# BuchlaBusBoard.net
KiCad netlist of a schematic drawn in Altium Designer
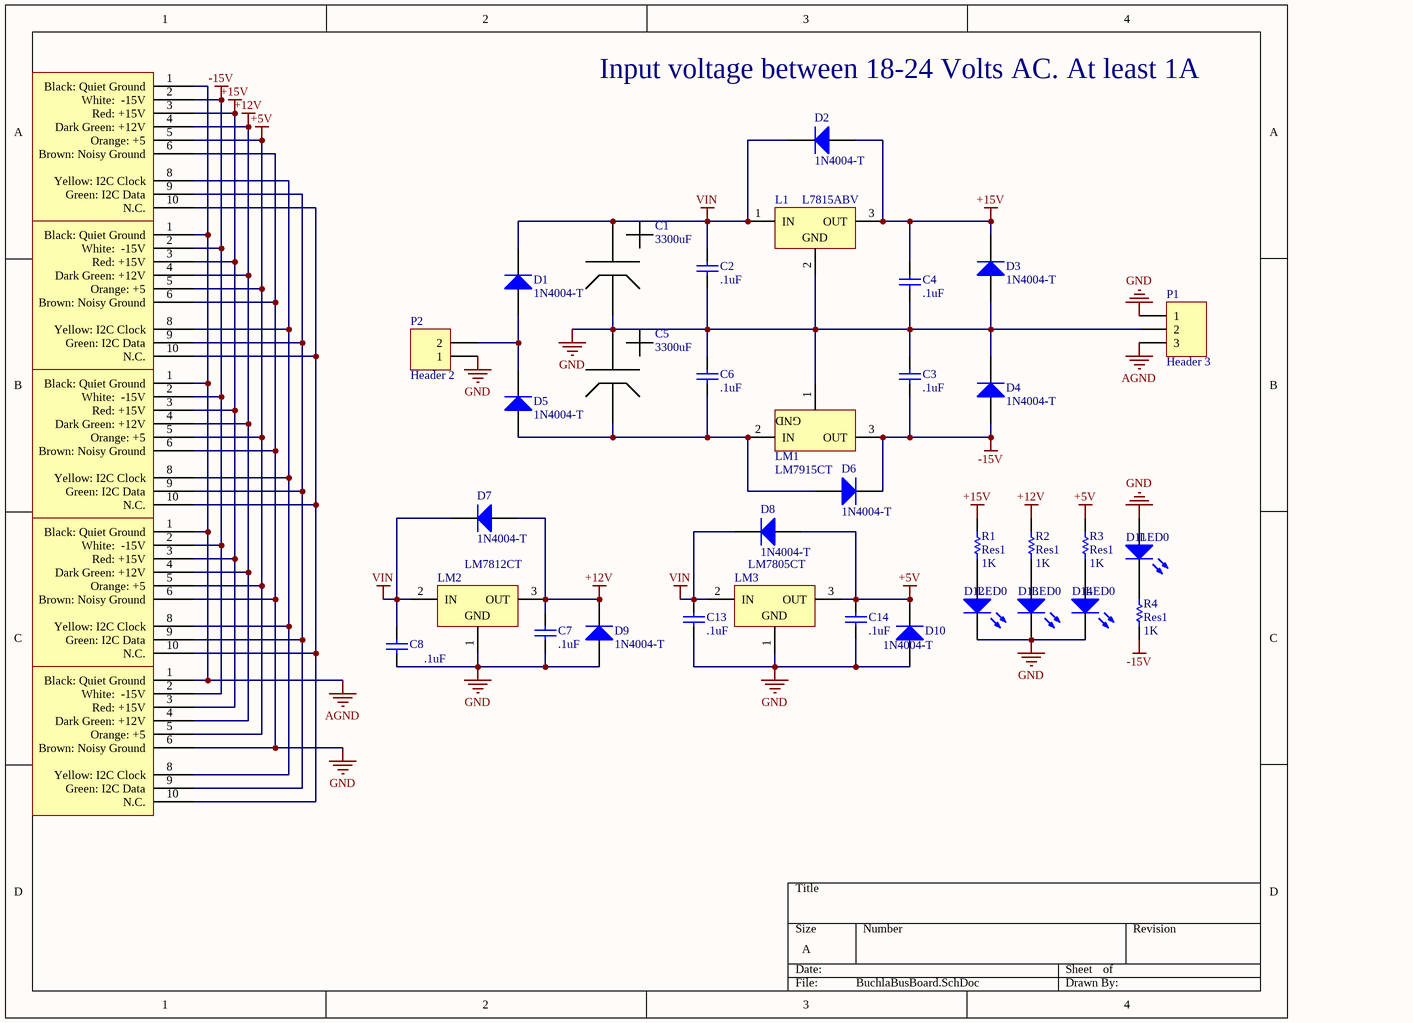
[diagram p0: BuchlaBusBoard.SchDoc]

(export (version "E")
  (design (tool "Eeschema 10.0.6"))
  (components
    (comp (ref "C1")
      (value "3300uF")
      (footprint "100uF")
      (description "100uF Electrolytic")
      (fields (field (name "MFR") "Illinois"))
      (libsource (lib "BuchlaBusBoardLibrary") (part "100uF Sprague"))
    )
    (comp (ref "C2")
      (value ".1uF")
      (footprint ".1uF")
      (description ".1uF Cap")
      (fields (field (name "MFR") "Vishay") (field (name "PUBLISHER") "Altium Limited"))
      (libsource (lib "Miscellaneous Devices") (part "Cap"))
    )
    (comp (ref "C3")
      (value ".1uF")
      (footprint ".1uF")
      (description ".1uF Cap")
      (fields (field (name "MFR") "Vishay") (field (name "PUBLISHER") "Altium Limited"))
      (libsource (lib "Miscellaneous Devices") (part "Cap"))
    )
    (comp (ref "C4")
      (value ".1uF")
      (footprint ".1uF")
      (description ".1uF Cap")
      (fields (field (name "MFR") "Vishay") (field (name "PUBLISHER") "Altium Limited"))
      (libsource (lib "Miscellaneous Devices") (part "Cap"))
    )
    (comp (ref "C5")
      (value "3300uF")
      (footprint "100uF")
      (description "100uF Electrolytic")
      (fields (field (name "MFR") "Illinois"))
      (libsource (lib "BuchlaBusBoardLibrary") (part "100uF Sprague"))
    )
    (comp (ref "C6")
      (value ".1uF")
      (footprint ".1uF")
      (description ".1uF Cap")
      (fields (field (name "MFR") "Vishay") (field (name "PUBLISHER") "Altium Limited"))
      (libsource (lib "Miscellaneous Devices") (part "Cap"))
    )
    (comp (ref "C7")
      (value ".1uF")
      (footprint ".1uF")
      (description ".1uF Cap")
      (fields (field (name "MFR") "Vishay") (field (name "PUBLISHER") "Altium Limited"))
      (libsource (lib "Miscellaneous Devices") (part "Cap"))
    )
    (comp (ref "C8")
      (value ".1uF")
      (footprint ".1uF")
      (description ".1uF Cap")
      (fields (field (name "MFR") "Vishay") (field (name "PUBLISHER") "Altium Limited"))
      (libsource (lib "Miscellaneous Devices") (part "Cap"))
    )
    (comp (ref "C13")
      (value ".1uF")
      (footprint ".1uF")
      (description ".1uF Cap")
      (fields (field (name "MFR") "Vishay") (field (name "PUBLISHER") "Altium Limited"))
      (libsource (lib "Miscellaneous Devices") (part "Cap"))
    )
    (comp (ref "C14")
      (value ".1uF")
      (footprint ".1uF")
      (description ".1uF Cap")
      (fields (field (name "MFR") "Vishay") (field (name "PUBLISHER") "Altium Limited"))
      (libsource (lib "Miscellaneous Devices") (part "Cap"))
    )
    (comp (ref "D1")
      (value "1N4004-T")
      (footprint "DIOD-DO-41-P-2_V")
      (description "1.0 A Rectifier, 15 pF, 50 V, -65 to 150 degC, 2-Pin DO-41 Plastic, RoHS, Tape and Reel")
      (fields (field (name "MFR") "Diodes Inc"))
      (libsource (lib "Altium Content Vault") (part "CMP-0639-00006-2"))
    )
    (comp (ref "D2")
      (value "1N4004-T")
      (footprint "DIOD-DO-41-P-2_V")
      (description "1.0 A Rectifier, 15 pF, 50 V, -65 to 150 degC, 2-Pin DO-41 Plastic, RoHS, Tape and Reel")
      (fields (field (name "MFR") "Diodes Inc"))
      (libsource (lib "Altium Content Vault") (part "CMP-0639-00006-2"))
    )
    (comp (ref "D3")
      (value "1N4004-T")
      (footprint "DIOD-DO-41-P-2_V")
      (description "1.0 A Rectifier, 15 pF, 50 V, -65 to 150 degC, 2-Pin DO-41 Plastic, RoHS, Tape and Reel")
      (fields (field (name "MFR") "Diodes Inc"))
      (libsource (lib "Altium Content Vault") (part "CMP-0639-00006-2"))
    )
    (comp (ref "D4")
      (value "1N4004-T")
      (footprint "DIOD-DO-41-P-2_V")
      (description "1.0 A Rectifier, 15 pF, 50 V, -65 to 150 degC, 2-Pin DO-41 Plastic, RoHS, Tape and Reel")
      (fields (field (name "MFR") "Diodes Inc"))
      (libsource (lib "Altium Content Vault") (part "CMP-0639-00006-2"))
    )
    (comp (ref "D5")
      (value "1N4004-T")
      (footprint "DIOD-DO-41-P-2_V")
      (description "1.0 A Rectifier, 15 pF, 50 V, -65 to 150 degC, 2-Pin DO-41 Plastic, RoHS, Tape and Reel")
      (fields (field (name "MFR") "Diodes Inc"))
      (libsource (lib "Altium Content Vault") (part "CMP-0639-00006-2"))
    )
    (comp (ref "D6")
      (value "1N4004-T")
      (footprint "DIOD-DO-41-P-2_V")
      (description "1.0 A Rectifier, 15 pF, 50 V, -65 to 150 degC, 2-Pin DO-41 Plastic, RoHS, Tape and Reel")
      (fields (field (name "MFR") "Diodes Inc"))
      (libsource (lib "Altium Content Vault") (part "CMP-0639-00006-2"))
    )
    (comp (ref "D7")
      (value "1N4004-T")
      (footprint "DIOD-DO-41-P-2_V")
      (description "1.0 A Rectifier, 15 pF, 50 V, -65 to 150 degC, 2-Pin DO-41 Plastic, RoHS, Tape and Reel")
      (fields (field (name "MFR") "Diodes Inc"))
      (libsource (lib "Altium Content Vault") (part "CMP-0639-00006-2"))
    )
    (comp (ref "D8")
      (value "1N4004-T")
      (footprint "DIOD-DO-41-P-2_V")
      (description "1.0 A Rectifier, 15 pF, 50 V, -65 to 150 degC, 2-Pin DO-41 Plastic, RoHS, Tape and Reel")
      (fields (field (name "MFR") "Diodes Inc"))
      (libsource (lib "Altium Content Vault") (part "CMP-0639-00006-2"))
    )
    (comp (ref "D9")
      (value "1N4004-T")
      (footprint "DIOD-DO-41-P-2_V")
      (description "1.0 A Rectifier, 15 pF, 50 V, -65 to 150 degC, 2-Pin DO-41 Plastic, RoHS, Tape and Reel")
      (fields (field (name "MFR") "Diodes Inc"))
      (libsource (lib "Altium Content Vault") (part "CMP-0639-00006-2"))
    )
    (comp (ref "D10")
      (value "1N4004-T")
      (footprint "DIOD-DO-41-P-2_V")
      (description "1.0 A Rectifier, 15 pF, 50 V, -65 to 150 degC, 2-Pin DO-41 Plastic, RoHS, Tape and Reel")
      (fields (field (name "MFR") "Diodes Inc"))
      (libsource (lib "Altium Content Vault") (part "CMP-0639-00006-2"))
    )
    (comp (ref "D11")
      (value "LED0")
      (footprint "LED-0")
      (description "Typical INFRARED GaAs LED")
      (fields (field (name "PUBLISHER") "Altium Limited"))
      (libsource (lib "Miscellaneous Devices") (part "LED0"))
    )
    (comp (ref "D12")
      (value "LED0")
      (footprint "LED-0")
      (description "Typical INFRARED GaAs LED")
      (fields (field (name "PUBLISHER") "Altium Limited"))
      (libsource (lib "Miscellaneous Devices") (part "LED0"))
    )
    (comp (ref "D13")
      (value "LED0")
      (footprint "LED-0")
      (description "Typical INFRARED GaAs LED")
      (fields (field (name "PUBLISHER") "Altium Limited"))
      (libsource (lib "Miscellaneous Devices") (part "LED0"))
    )
    (comp (ref "D14")
      (value "LED0")
      (footprint "LED-0")
      (description "Typical INFRARED GaAs LED")
      (fields (field (name "PUBLISHER") "Altium Limited"))
      (libsource (lib "Miscellaneous Devices") (part "LED0"))
    )
    (comp (ref "L1")
      (value "L7815ABV")
      (footprint "TO220")
      (description "15V Positive Regulator")
      (fields (field (name "MFR") "ST"))
      (libsource (lib "Altium Content Vault") (part "CMP-0244-00468-1"))
    )
    (comp (ref "LM1")
      (value "LM7915CT")
      (footprint "NDE0003A")
      (description "3-Terminal Negative Regulator, 3-pin TO-220")
      (fields (field (name "MANUFACTURER") "Texas Instruments"))
      (libsource (lib "altium-import") (part "root_2_mirrored_CMP-0062-02471-3_"))
    )
    (comp (ref "LM2")
      (value "LM7812CT")
      (footprint "NDE0003A")
      (description "3-Terminal Negative Regulator, 3-pin TO-220")
      (fields (field (name "MANUFACTURER") "Texas Instruments"))
      (libsource (lib "altium-import") (part "root_0_CMP-0062-02471-3_"))
    )
    (comp (ref "LM3")
      (value "LM7805CT")
      (footprint "NDE0003A")
      (description "3-Terminal Negative Regulator, 3-pin TO-220")
      (fields (field (name "MANUFACTURER") "Texas Instruments"))
      (libsource (lib "altium-import") (part "root_0_CMP-0062-02471-3_"))
    )
    (comp (ref "P1")
      (value "Header 3")
      (footprint "HDR1X3")
      (description "Header, 3-Pin")
      (fields (field (name "PUBLISHER") "Altium Limited"))
      (libsource (lib "Miscellaneous Connectors") (part "Header 3"))
    )
    (comp (ref "P2")
      (value "Header 2")
      (footprint "HDR1X2")
      (description "Header, 2-Pin")
      (fields (field (name "PUBLISHER") "Altium Limited"))
      (libsource (lib "Miscellaneous Connectors") (part "Header 2"))
    )
    (comp (ref "R1")
      (value "Res1")
      (footprint "AXIAL-0.3")
      (description "Resistor")
      (fields (field (name "ALTIUM_VALUE") "1K") (field (name "PUBLISHER") "Altium Limited"))
      (libsource (lib "Miscellaneous Devices") (part "Res1"))
    )
    (comp (ref "R2")
      (value "Res1")
      (footprint "AXIAL-0.3")
      (description "Resistor")
      (fields (field (name "ALTIUM_VALUE") "1K") (field (name "PUBLISHER") "Altium Limited"))
      (libsource (lib "Miscellaneous Devices") (part "Res1"))
    )
    (comp (ref "R3")
      (value "Res1")
      (footprint "AXIAL-0.3")
      (description "Resistor")
      (fields (field (name "ALTIUM_VALUE") "1K") (field (name "PUBLISHER") "Altium Limited"))
      (libsource (lib "Miscellaneous Devices") (part "Res1"))
    )
    (comp (ref "R4")
      (value "Res1")
      (footprint "AXIAL-0.3")
      (description "Resistor")
      (fields (field (name "ALTIUM_VALUE") "1K") (field (name "PUBLISHER") "Altium Limited"))
      (libsource (lib "Miscellaneous Devices") (part "Res1"))
    )
    (comp (ref "Vag1")
      (value "Component_1")
      (footprint "BuchlaPower")
      (libsource (lib "BuchlaBusBoardLibrary") (part "Component_1"))
    )
    (comp (ref "Vag2")
      (value "Component_1")
      (footprint "BuchlaPower")
      (libsource (lib "BuchlaBusBoardLibrary") (part "Component_1"))
    )
    (comp (ref "Vag5")
      (value "Component_1")
      (footprint "BuchlaPower")
      (libsource (lib "BuchlaBusBoardLibrary") (part "Component_1"))
    )
    (comp (ref "Vag6")
      (value "Component_1")
      (footprint "BuchlaPower")
      (libsource (lib "BuchlaBusBoardLibrary") (part "Component_1"))
    )
    (comp (ref "Vag7")
      (value "Component_1")
      (footprint "BuchlaPower")
      (libsource (lib "BuchlaBusBoardLibrary") (part "Component_1"))
    )
  )
  (nets
    (net (code "1") (name "+5V") (class "Default")
      (node (ref "C14") (pin "2") (pinfunction "2_2") (pintype "passive"))
      (node (ref "D10") (pin "2") (pinfunction "K_2") (pintype "passive"))
      (node (ref "D8") (pin "1") (pinfunction "A_1") (pintype "passive"))
      (node (ref "LM3") (pin "3") (pinfunction "OUT_3") (pintype "power_in"))
      (node (ref "R3") (pin "2") (pinfunction "2_2") (pintype "passive"))
      (node (ref "Vag1") (pin "5") (pinfunction "Orange:_+5_5") (pintype "passive"))
      (node (ref "Vag2") (pin "5") (pinfunction "Orange:_+5_5") (pintype "passive"))
      (node (ref "Vag5") (pin "5") (pinfunction "Orange:_+5_5") (pintype "passive"))
      (node (ref "Vag6") (pin "5") (pinfunction "Orange:_+5_5") (pintype "passive"))
      (node (ref "Vag7") (pin "5") (pinfunction "Orange:_+5_5") (pintype "passive"))
    )
    (net (code "2") (name "+12V") (class "Default")
      (node (ref "C7") (pin "2") (pinfunction "2_2") (pintype "passive"))
      (node (ref "D7") (pin "1") (pinfunction "A_1") (pintype "passive"))
      (node (ref "D9") (pin "2") (pinfunction "K_2") (pintype "passive"))
      (node (ref "LM2") (pin "3") (pinfunction "OUT_3") (pintype "power_in"))
      (node (ref "R2") (pin "2") (pinfunction "2_2") (pintype "passive"))
      (node (ref "Vag1") (pin "4") (pinfunction "Dark_Green:_+12V_4") (pintype "passive"))
      (node (ref "Vag2") (pin "4") (pinfunction "Dark_Green:_+12V_4") (pintype "passive"))
      (node (ref "Vag5") (pin "4") (pinfunction "Dark_Green:_+12V_4") (pintype "passive"))
      (node (ref "Vag6") (pin "4") (pinfunction "Dark_Green:_+12V_4") (pintype "passive"))
      (node (ref "Vag7") (pin "4") (pinfunction "Dark_Green:_+12V_4") (pintype "passive"))
    )
    (net (code "3") (name "+15V") (class "Default")
      (node (ref "C4") (pin "2") (pinfunction "2_2") (pintype "passive"))
      (node (ref "D2") (pin "1") (pinfunction "A_1") (pintype "passive"))
      (node (ref "D3") (pin "2") (pinfunction "K_2") (pintype "passive"))
      (node (ref "L1") (pin "3") (pinfunction "OUT_3") (pintype "power_in"))
      (node (ref "R1") (pin "2") (pinfunction "2_2") (pintype "passive"))
      (node (ref "Vag1") (pin "3") (pinfunction "Red:_+15V_3") (pintype "passive"))
      (node (ref "Vag2") (pin "3") (pinfunction "Red:_+15V_3") (pintype "passive"))
      (node (ref "Vag5") (pin "3") (pinfunction "Red:_+15V_3") (pintype "passive"))
      (node (ref "Vag6") (pin "3") (pinfunction "Red:_+15V_3") (pintype "passive"))
      (node (ref "Vag7") (pin "3") (pinfunction "Red:_+15V_3") (pintype "passive"))
    )
    (net (code "4") (name "-15V") (class "Default")
      (node (ref "C3") (pin "1") (pinfunction "1_1") (pintype "passive"))
      (node (ref "D4") (pin "1") (pinfunction "A_1") (pintype "passive"))
      (node (ref "D6") (pin "2") (pinfunction "K_2") (pintype "passive"))
      (node (ref "LM1") (pin "3") (pinfunction "OUT_3") (pintype "power_in"))
      (node (ref "R4") (pin "1") (pinfunction "1_1") (pintype "passive"))
      (node (ref "Vag1") (pin "2") (pinfunction "White:__-15V_2") (pintype "passive"))
      (node (ref "Vag2") (pin "2") (pinfunction "White:__-15V_2") (pintype "passive"))
      (node (ref "Vag5") (pin "2") (pinfunction "White:__-15V_2") (pintype "passive"))
      (node (ref "Vag6") (pin "2") (pinfunction "White:__-15V_2") (pintype "passive"))
      (node (ref "Vag7") (pin "2") (pinfunction "White:__-15V_2") (pintype "passive"))
    )
    (net (code "5") (name "AGND") (class "Default")
      (node (ref "P1") (pin "3") (pinfunction "3_3") (pintype "passive"))
      (node (ref "Vag1") (pin "1") (pinfunction "Black:_Quiet_Ground_1") (pintype "passive"))
      (node (ref "Vag2") (pin "1") (pinfunction "Black:_Quiet_Ground_1") (pintype "passive"))
      (node (ref "Vag5") (pin "1") (pinfunction "Black:_Quiet_Ground_1") (pintype "passive"))
      (node (ref "Vag6") (pin "1") (pinfunction "Black:_Quiet_Ground_1") (pintype "passive"))
      (node (ref "Vag7") (pin "1") (pinfunction "Black:_Quiet_Ground_1") (pintype "passive"))
    )
    (net (code "6") (name "GND") (class "Default")
      (node (ref "C1") (pin "1") (pinfunction "33_1") (pintype "passive"))
      (node (ref "C13") (pin "1") (pinfunction "1_1") (pintype "passive"))
      (node (ref "C14") (pin "1") (pinfunction "1_1") (pintype "passive"))
      (node (ref "C2") (pin "1") (pinfunction "1_1") (pintype "passive"))
      (node (ref "C3") (pin "2") (pinfunction "2_2") (pintype "passive"))
      (node (ref "C4") (pin "1") (pinfunction "1_1") (pintype "passive"))
      (node (ref "C5") (pin "0") (pinfunction "32_0") (pintype "passive"))
      (node (ref "C6") (pin "2") (pinfunction "2_2") (pintype "passive"))
      (node (ref "C7") (pin "1") (pinfunction "1_1") (pintype "passive"))
      (node (ref "C8") (pin "1") (pinfunction "1_1") (pintype "passive"))
      (node (ref "D10") (pin "1") (pinfunction "A_1") (pintype "passive"))
      (node (ref "D11") (pin "1") (pinfunction "A_1") (pintype "passive"))
      (node (ref "D12") (pin "2") (pinfunction "K_2") (pintype "passive"))
      (node (ref "D13") (pin "2") (pinfunction "K_2") (pintype "passive"))
      (node (ref "D14") (pin "2") (pinfunction "K_2") (pintype "passive"))
      (node (ref "D3") (pin "1") (pinfunction "A_1") (pintype "passive"))
      (node (ref "D4") (pin "2") (pinfunction "K_2") (pintype "passive"))
      (node (ref "D9") (pin "1") (pinfunction "A_1") (pintype "passive"))
      (node (ref "L1") (pin "2") (pinfunction "GND_2") (pintype "power_in"))
      (node (ref "LM1") (pin "1") (pinfunction "GND_1") (pintype "power_in"))
      (node (ref "LM2") (pin "1") (pinfunction "GND_1") (pintype "power_in"))
      (node (ref "LM3") (pin "1") (pinfunction "GND_1") (pintype "power_in"))
      (node (ref "P1") (pin "1") (pinfunction "1_1") (pintype "passive"))
      (node (ref "P1") (pin "2") (pinfunction "2_2") (pintype "passive"))
      (node (ref "P2") (pin "1") (pinfunction "1_1") (pintype "passive"))
      (node (ref "Vag1") (pin "6") (pinfunction "Brown:_Noisy_Ground_6") (pintype "passive"))
      (node (ref "Vag2") (pin "6") (pinfunction "Brown:_Noisy_Ground_6") (pintype "passive"))
      (node (ref "Vag5") (pin "6") (pinfunction "Brown:_Noisy_Ground_6") (pintype "passive"))
      (node (ref "Vag6") (pin "6") (pinfunction "Brown:_Noisy_Ground_6") (pintype "passive"))
      (node (ref "Vag7") (pin "6") (pinfunction "Brown:_Noisy_Ground_6") (pintype "passive"))
    )
    (net (code "7") (name "Net-(C5-33)") (class "Default")
      (node (ref "C5") (pin "1") (pinfunction "33_1") (pintype "passive"))
      (node (ref "C6") (pin "1") (pinfunction "1_1") (pintype "passive"))
      (node (ref "D5") (pin "1") (pinfunction "A_1") (pintype "passive"))
      (node (ref "D6") (pin "1") (pinfunction "A_1") (pintype "passive"))
      (node (ref "LM1") (pin "2") (pinfunction "IN_2") (pintype "power_in"))
    )
    (net (code "8") (name "Net-(D1-A)") (class "Default")
      (node (ref "D1") (pin "1") (pinfunction "A_1") (pintype "passive"))
      (node (ref "D5") (pin "2") (pinfunction "K_2") (pintype "passive"))
      (node (ref "P2") (pin "2") (pinfunction "2_2") (pintype "passive"))
    )
    (net (code "9") (name "Net-(D11-K)") (class "Default")
      (node (ref "D11") (pin "2") (pinfunction "K_2") (pintype "passive"))
      (node (ref "R4") (pin "2") (pinfunction "2_2") (pintype "passive"))
    )
    (net (code "10") (name "Net-(D12-A)") (class "Default")
      (node (ref "D12") (pin "1") (pinfunction "A_1") (pintype "passive"))
      (node (ref "R1") (pin "1") (pinfunction "1_1") (pintype "passive"))
    )
    (net (code "11") (name "Net-(D13-A)") (class "Default")
      (node (ref "D13") (pin "1") (pinfunction "A_1") (pintype "passive"))
      (node (ref "R2") (pin "1") (pinfunction "1_1") (pintype "passive"))
    )
    (net (code "12") (name "Net-(D14-A)") (class "Default")
      (node (ref "D14") (pin "1") (pinfunction "A_1") (pintype "passive"))
      (node (ref "R3") (pin "1") (pinfunction "1_1") (pintype "passive"))
    )
    (net (code "13") (name "Net-(Vag1-Green:_I2C_Data)") (class "Default")
      (node (ref "Vag1") (pin "9") (pinfunction "Green:_I2C_Data_9") (pintype "passive"))
      (node (ref "Vag2") (pin "9") (pinfunction "Green:_I2C_Data_9") (pintype "passive"))
      (node (ref "Vag5") (pin "9") (pinfunction "Green:_I2C_Data_9") (pintype "passive"))
      (node (ref "Vag6") (pin "9") (pinfunction "Green:_I2C_Data_9") (pintype "passive"))
      (node (ref "Vag7") (pin "9") (pinfunction "Green:_I2C_Data_9") (pintype "passive"))
    )
    (net (code "14") (name "Net-(Vag1-N.C.)") (class "Default")
      (node (ref "Vag1") (pin "10") (pinfunction "N.C._10") (pintype "passive"))
      (node (ref "Vag2") (pin "10") (pinfunction "N.C._10") (pintype "passive"))
      (node (ref "Vag5") (pin "10") (pinfunction "N.C._10") (pintype "passive"))
      (node (ref "Vag6") (pin "10") (pinfunction "N.C._10") (pintype "passive"))
      (node (ref "Vag7") (pin "10") (pinfunction "N.C._10") (pintype "passive"))
    )
    (net (code "15") (name "Net-(Vag1-Yellow:_I2C_Clock)") (class "Default")
      (node (ref "Vag1") (pin "8") (pinfunction "Yellow:_I2C_Clock_8") (pintype "passive"))
      (node (ref "Vag2") (pin "8") (pinfunction "Yellow:_I2C_Clock_8") (pintype "passive"))
      (node (ref "Vag5") (pin "8") (pinfunction "Yellow:_I2C_Clock_8") (pintype "passive"))
      (node (ref "Vag6") (pin "8") (pinfunction "Yellow:_I2C_Clock_8") (pintype "passive"))
      (node (ref "Vag7") (pin "8") (pinfunction "Yellow:_I2C_Clock_8") (pintype "passive"))
    )
    (net (code "16") (name "VIN") (class "Default")
      (node (ref "C1") (pin "0") (pinfunction "32_0") (pintype "passive"))
      (node (ref "C13") (pin "2") (pinfunction "2_2") (pintype "passive"))
      (node (ref "C2") (pin "2") (pinfunction "2_2") (pintype "passive"))
      (node (ref "C8") (pin "2") (pinfunction "2_2") (pintype "passive"))
      (node (ref "D1") (pin "2") (pinfunction "K_2") (pintype "passive"))
      (node (ref "D2") (pin "2") (pinfunction "K_2") (pintype "passive"))
      (node (ref "D7") (pin "2") (pinfunction "K_2") (pintype "passive"))
      (node (ref "D8") (pin "2") (pinfunction "K_2") (pintype "passive"))
      (node (ref "L1") (pin "1") (pinfunction "IN_1") (pintype "power_in"))
      (node (ref "LM2") (pin "2") (pinfunction "IN_2") (pintype "power_in"))
      (node (ref "LM3") (pin "2") (pinfunction "IN_2") (pintype "power_in"))
    )
  )
)
